# MESH-Grove.net
KiCad netlist of a schematic drawn in EAGLE
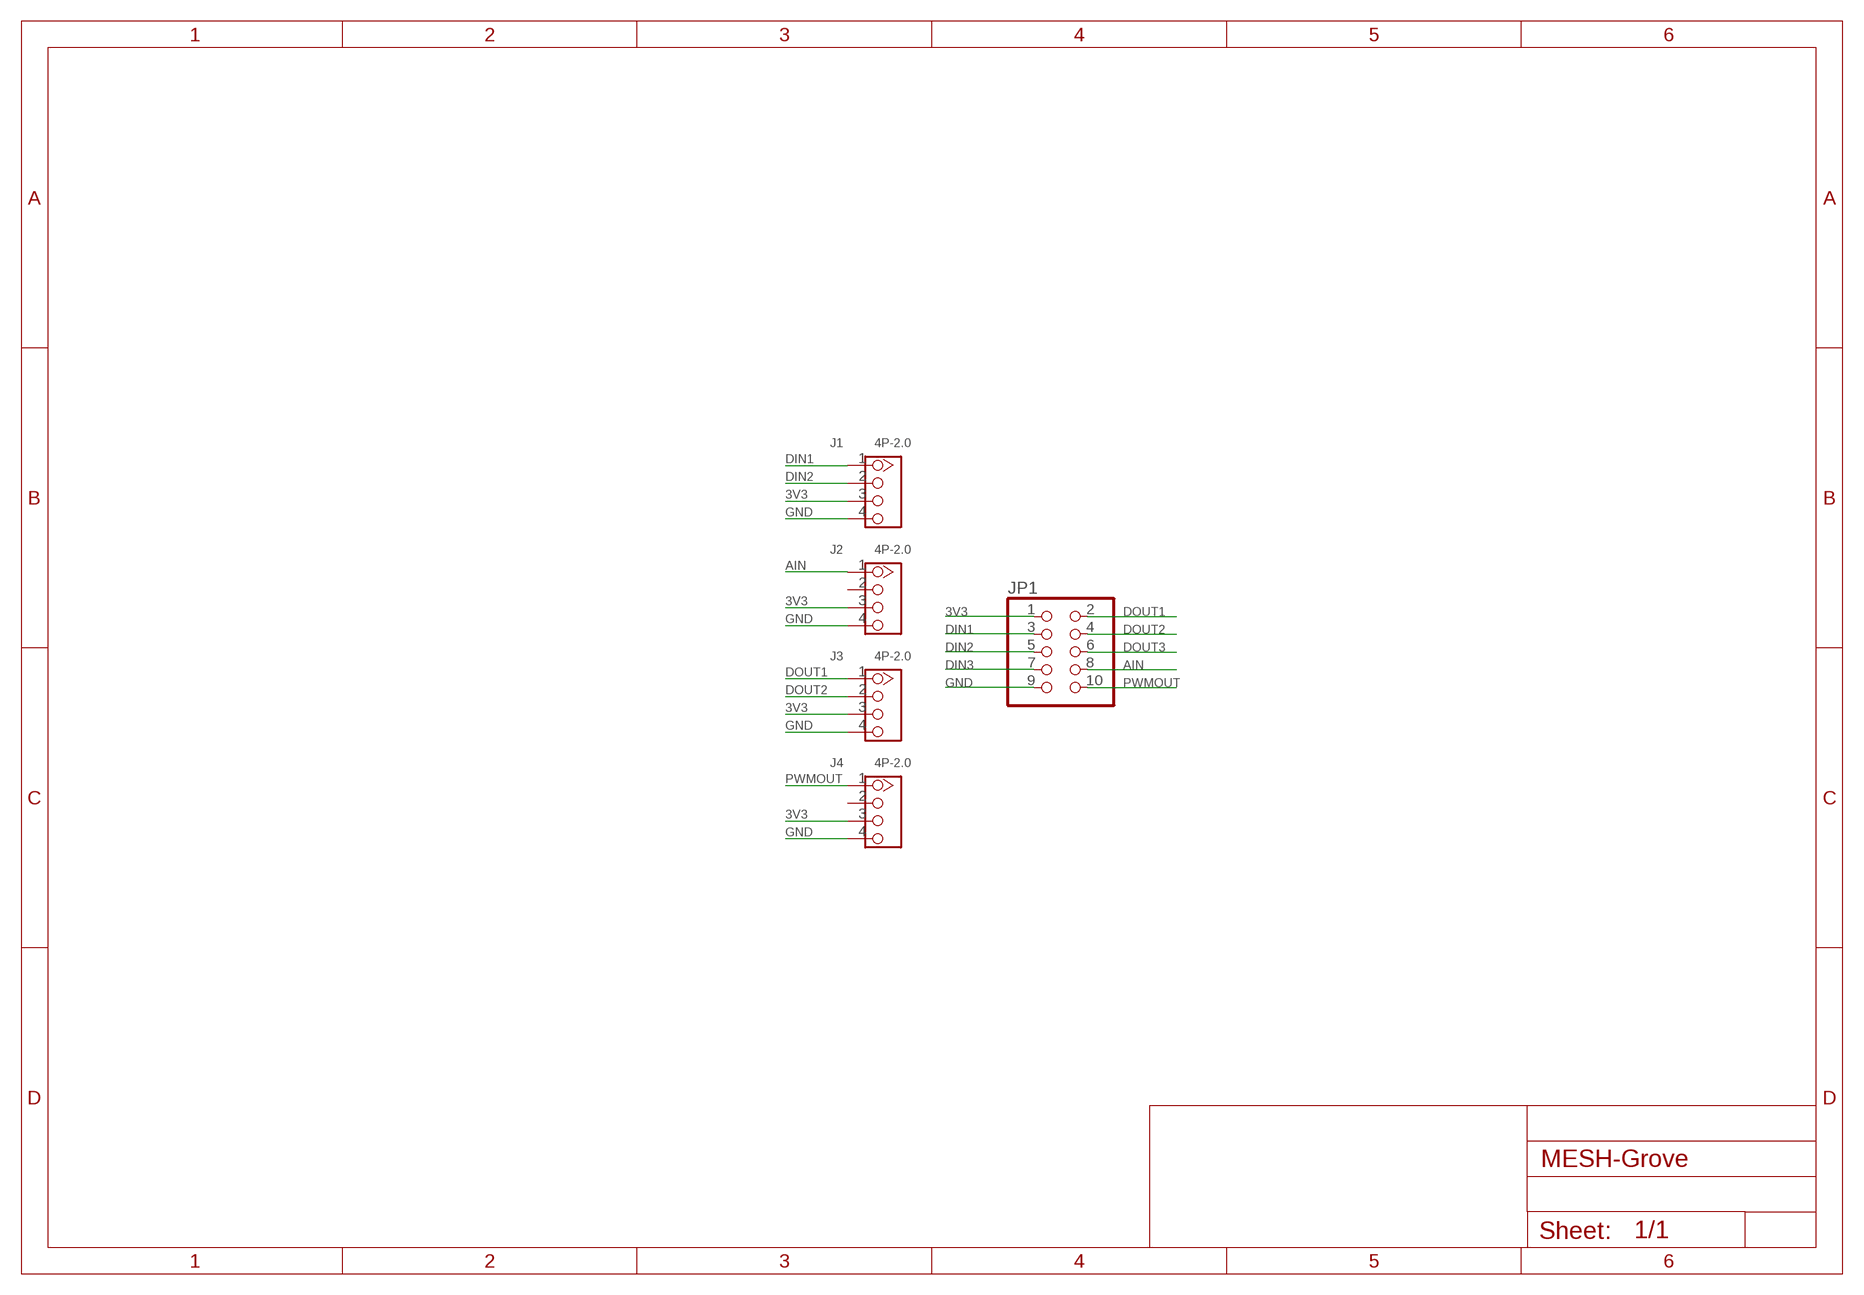
[diagram p0: schematic, sheet 1]

(export (version "E")
  (design (tool "Eeschema 10.0.6"))
  (components
    (comp (ref "J1")
      (value "4P-2.0")
      (footprint "eagle-import:HW4-2.0")
      (libsource (lib "eagle-import") (part "GROVE-CONNECTOR-DIP(4P-2.0)"))
    )
    (comp (ref "J2")
      (value "4P-2.0")
      (footprint "eagle-import:HW4-2.0")
      (libsource (lib "eagle-import") (part "GROVE-CONNECTOR-DIP(4P-2.0)"))
    )
    (comp (ref "J3")
      (value "4P-2.0")
      (footprint "eagle-import:HW4-2.0")
      (libsource (lib "eagle-import") (part "GROVE-CONNECTOR-DIP(4P-2.0)"))
    )
    (comp (ref "J4")
      (value "4P-2.0")
      (footprint "eagle-import:HW4-2.0")
      (libsource (lib "eagle-import") (part "GROVE-CONNECTOR-DIP(4P-2.0)"))
    )
    (comp (ref "JP1")
      (value "PINHD-2X5")
      (footprint "eagle-import:2X05")
      (libsource (lib "eagle-import") (part "PINHD-2X5"))
    )
  )
  (nets
    (net (code "1") (name "/3V3") (class "Default")
      (node (ref "J1") (pin "3") (pinfunction "3_3") (pintype "bidirectional"))
      (node (ref "J2") (pin "3") (pinfunction "3_3") (pintype "bidirectional"))
      (node (ref "J3") (pin "3") (pinfunction "3_3") (pintype "bidirectional"))
      (node (ref "J4") (pin "3") (pinfunction "3_3") (pintype "bidirectional"))
      (node (ref "JP1") (pin "1") (pinfunction "1_1") (pintype "passive"))
    )
    (net (code "2") (name "/AIN") (class "Default")
      (node (ref "J2") (pin "1") (pinfunction "1_1") (pintype "bidirectional"))
      (node (ref "JP1") (pin "8") (pinfunction "8_8") (pintype "passive"))
    )
    (net (code "3") (name "/DIN1") (class "Default")
      (node (ref "J1") (pin "1") (pinfunction "1_1") (pintype "bidirectional"))
      (node (ref "JP1") (pin "3") (pinfunction "3_3") (pintype "passive"))
    )
    (net (code "4") (name "/DIN2") (class "Default")
      (node (ref "J1") (pin "2") (pinfunction "2_2") (pintype "bidirectional"))
      (node (ref "JP1") (pin "5") (pinfunction "5_5") (pintype "passive"))
    )
    (net (code "5") (name "/DIN3") (class "Default")
      (node (ref "JP1") (pin "7") (pinfunction "7_7") (pintype "passive"))
    )
    (net (code "6") (name "/DOUT1") (class "Default")
      (node (ref "J3") (pin "1") (pinfunction "1_1") (pintype "bidirectional"))
      (node (ref "JP1") (pin "2") (pinfunction "2_2") (pintype "passive"))
    )
    (net (code "7") (name "/DOUT2") (class "Default")
      (node (ref "J3") (pin "2") (pinfunction "2_2") (pintype "bidirectional"))
      (node (ref "JP1") (pin "4") (pinfunction "4_4") (pintype "passive"))
    )
    (net (code "8") (name "/DOUT3") (class "Default")
      (node (ref "JP1") (pin "6") (pinfunction "6_6") (pintype "passive"))
    )
    (net (code "9") (name "/GND") (class "Default")
      (node (ref "J1") (pin "4") (pinfunction "4_4") (pintype "bidirectional"))
      (node (ref "J2") (pin "4") (pinfunction "4_4") (pintype "bidirectional"))
      (node (ref "J3") (pin "4") (pinfunction "4_4") (pintype "bidirectional"))
      (node (ref "J4") (pin "4") (pinfunction "4_4") (pintype "bidirectional"))
      (node (ref "JP1") (pin "9") (pinfunction "9_9") (pintype "passive"))
    )
    (net (code "10") (name "/PWMOUT") (class "Default")
      (node (ref "J4") (pin "1") (pinfunction "1_1") (pintype "bidirectional"))
      (node (ref "JP1") (pin "10") (pinfunction "10_10") (pintype "passive"))
    )
    (net (code "11") (name "unconnected-(J2-Pad2)") (class "Default")
      (node (ref "J2") (pin "2") (pinfunction "2_2") (pintype "bidirectional"))
    )
    (net (code "12") (name "unconnected-(J4-Pad2)") (class "Default")
      (node (ref "J4") (pin "2") (pinfunction "2_2") (pintype "bidirectional"))
    )
  )
)
